# JTAG.net
KiCad netlist of a schematic drawn in Altium Designer
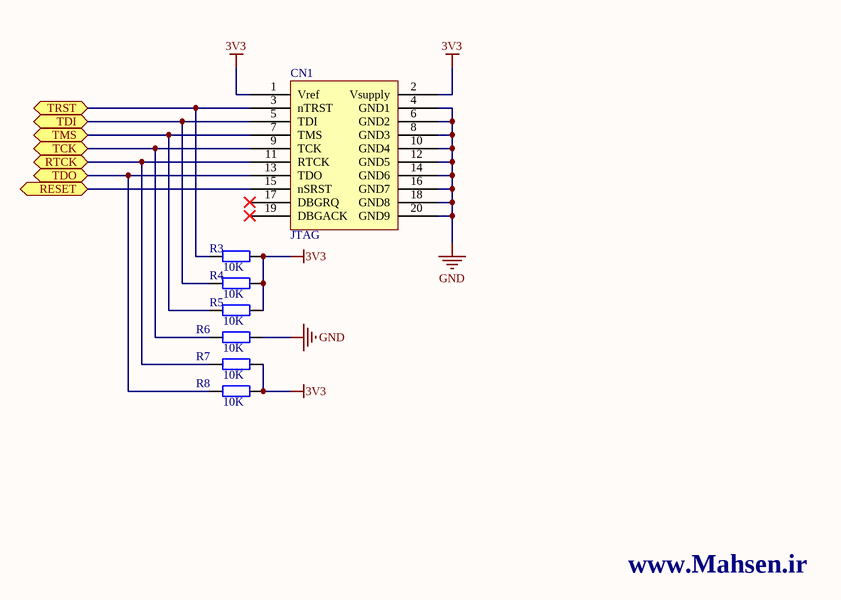
[diagram p0: JTAG.SchDoc]

(export (version "E")
  (design (tool "Eeschema 10.0.6"))
  (components
    (comp (ref "CN1") (value "JTAG") (footprint "FKV20SN") (libsource (lib "Lotfi") (part "JTAG")))
    (comp (ref "R3")
      (value "10K")
      (footprint "0805")
      (description "Resistor")
      (fields (field (name "PUBLISHER") "Altium Limited"))
      (libsource (lib "Miscellaneous Devices") (part "Res2"))
    )
    (comp (ref "R4")
      (value "10K")
      (footprint "0805")
      (description "Resistor")
      (fields (field (name "PUBLISHER") "Altium Limited"))
      (libsource (lib "Miscellaneous Devices") (part "Res2"))
    )
    (comp (ref "R5")
      (value "10K")
      (footprint "0805")
      (description "Resistor")
      (fields (field (name "PUBLISHER") "Altium Limited"))
      (libsource (lib "Miscellaneous Devices") (part "Res2"))
    )
    (comp (ref "R6")
      (value "10K")
      (footprint "0805")
      (description "Resistor")
      (fields (field (name "PUBLISHER") "Altium Limited"))
      (libsource (lib "Miscellaneous Devices") (part "Res2"))
    )
    (comp (ref "R7")
      (value "10K")
      (footprint "0805")
      (description "Resistor")
      (fields (field (name "PUBLISHER") "Altium Limited"))
      (libsource (lib "Miscellaneous Devices") (part "Res2"))
    )
    (comp (ref "R8")
      (value "10K")
      (footprint "0805")
      (description "Resistor")
      (fields (field (name "PUBLISHER") "Altium Limited"))
      (libsource (lib "Miscellaneous Devices") (part "Res2"))
    )
  )
  (nets
    (net (code "1") (name "/RESET") (class "Default")
      (node (ref "CN1") (pin "15") (pinfunction "nSRST_15") (pintype "passive"))
    )
    (net (code "2") (name "/RTCK") (class "Default")
      (node (ref "CN1") (pin "11") (pinfunction "RTCK_11") (pintype "passive"))
      (node (ref "R7") (pin "2") (pinfunction "2_2") (pintype "passive"))
    )
    (net (code "3") (name "/TCK") (class "Default")
      (node (ref "CN1") (pin "9") (pinfunction "TCK_9") (pintype "passive"))
      (node (ref "R6") (pin "2") (pinfunction "2_2") (pintype "passive"))
    )
    (net (code "4") (name "/TDI") (class "Default")
      (node (ref "CN1") (pin "5") (pinfunction "TDI_5") (pintype "passive"))
      (node (ref "R4") (pin "2") (pinfunction "2_2") (pintype "passive"))
    )
    (net (code "5") (name "/TDO") (class "Default")
      (node (ref "CN1") (pin "13") (pinfunction "TDO_13") (pintype "passive"))
      (node (ref "R8") (pin "2") (pinfunction "2_2") (pintype "passive"))
    )
    (net (code "6") (name "/TMS") (class "Default")
      (node (ref "CN1") (pin "7") (pinfunction "TMS_7") (pintype "passive"))
      (node (ref "R5") (pin "2") (pinfunction "2_2") (pintype "passive"))
    )
    (net (code "7") (name "/TRST") (class "Default")
      (node (ref "CN1") (pin "3") (pinfunction "nTRST_3") (pintype "passive"))
      (node (ref "R3") (pin "2") (pinfunction "2_2") (pintype "passive"))
    )
    (net (code "8") (name "3V3") (class "Default")
      (node (ref "CN1") (pin "1") (pinfunction "Vref_1") (pintype "passive"))
      (node (ref "CN1") (pin "2") (pinfunction "Vsupply_2") (pintype "passive"))
      (node (ref "R3") (pin "1") (pinfunction "1_1") (pintype "passive"))
      (node (ref "R4") (pin "1") (pinfunction "1_1") (pintype "passive"))
      (node (ref "R5") (pin "1") (pinfunction "1_1") (pintype "passive"))
      (node (ref "R7") (pin "1") (pinfunction "1_1") (pintype "passive"))
      (node (ref "R8") (pin "1") (pinfunction "1_1") (pintype "passive"))
    )
    (net (code "9") (name "GND") (class "Default")
      (node (ref "CN1") (pin "10") (pinfunction "GND4_10") (pintype "passive"))
      (node (ref "CN1") (pin "12") (pinfunction "GND5_12") (pintype "passive"))
      (node (ref "CN1") (pin "14") (pinfunction "GND6_14") (pintype "passive"))
      (node (ref "CN1") (pin "16") (pinfunction "GND7_16") (pintype "passive"))
      (node (ref "CN1") (pin "18") (pinfunction "GND8_18") (pintype "passive"))
      (node (ref "CN1") (pin "20") (pinfunction "GND9_20") (pintype "passive"))
      (node (ref "CN1") (pin "4") (pinfunction "GND1_4") (pintype "passive"))
      (node (ref "CN1") (pin "6") (pinfunction "GND2_6") (pintype "passive"))
      (node (ref "CN1") (pin "8") (pinfunction "GND3_8") (pintype "passive"))
      (node (ref "R6") (pin "1") (pinfunction "1_1") (pintype "passive"))
    )
    (net (code "10") (name "unconnected-(CN1-DBGACK-Pad19)") (class "Default")
      (node (ref "CN1") (pin "19") (pinfunction "DBGACK_19") (pintype "passive+no_connect"))
    )
    (net (code "11") (name "unconnected-(CN1-DBGRQ-Pad17)") (class "Default")
      (node (ref "CN1") (pin "17") (pinfunction "DBGRQ_17") (pintype "passive+no_connect"))
    )
  )
)
